# FaultOptoNC.net
KiCad netlist of a schematic drawn in Altium Designer
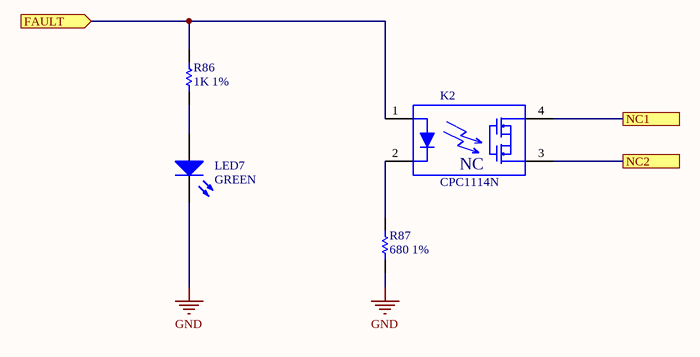
[diagram p0: FaultOptoNC.SchDoc]

(export (version "E")
  (design (tool "Eeschema 10.0.6"))
  (components
    (comp (ref "K2")
      (value "CPC1114N")
      (footprint "MC1:SOP254P610X206-4N")
      (description "SINGLE-POLE, NORMALLY CLOSED4-LEAD SOP OPTOMOS RELAY")
      (fields (field (name "MANUFACTURER") "Ixys Clare"))
      (libsource (lib "MC1") (part "CPC1114N"))
    )
    (comp (ref "LED7")
      (value "GREEN")
      (footprint "LED0805")
      (description "LED GREEN CLEAR 0805 SMD")
      (fields
        (field (name "MANUFACTURER") "Wurth Electronics")
        (field (name "MANUFACTURER PART NUMBER") "150080VS75000")
      )
      (libsource (lib "MCx") (part "150080VS75000"))
    )
    (comp (ref "R86")
      (value "1K 1%")
      (footprint "R0805")
      (fields
        (field (name "MANUFACTURER") "Yageo")
        (field (name "MANUFACTURER PART NUMBER") "RC0805FR-071KL")
        (field (name "TOLERANCE") "1%")
      )
      (libsource (lib "MCx") (part "RC0805FR-071KL"))
    )
    (comp (ref "R87")
      (value "680 1%")
      (footprint "R0805")
      (fields
        (field (name "MANUFACTURER") "Panasonic")
        (field (name "MANUFACTURER PART NUMBER") "ERJ6ENF6800V")
        (field (name "TOLERANCE") "1%")
      )
      (libsource (lib "MCx") (part "ERJ6ENF6800V"))
    )
  )
  (nets
    (net (code "1") (name "/FAULT") (class "Default")
      (node (ref "K2") (pin "1") (pinfunction "1_1") (pintype "passive"))
      (node (ref "R86") (pin "1") (pinfunction "1_1") (pintype "passive"))
    )
    (net (code "2") (name "/NC1") (class "Default")
      (node (ref "K2") (pin "4") (pinfunction "4_4") (pintype "passive"))
    )
    (net (code "3") (name "/NC2") (class "Default")
      (node (ref "K2") (pin "3") (pinfunction "3_3") (pintype "passive"))
    )
    (net (code "4") (name "GND") (class "Default")
      (node (ref "LED7") (pin "1") (pinfunction "K_1") (pintype "passive"))
      (node (ref "R87") (pin "1") (pinfunction "1_1") (pintype "passive"))
    )
    (net (code "5") (name "Net-(K2-Pad2)") (class "Default")
      (node (ref "K2") (pin "2") (pinfunction "2_2") (pintype "passive"))
      (node (ref "R87") (pin "2") (pinfunction "2_2") (pintype "passive"))
    )
    (net (code "6") (name "Net-(LED7-A)") (class "Default")
      (node (ref "LED7") (pin "2") (pinfunction "A_2") (pintype "passive"))
      (node (ref "R86") (pin "2") (pinfunction "2_2") (pintype "passive"))
    )
  )
)
